# Low_Pass_Filter.net
KiCad netlist of a schematic drawn in Altium Designer
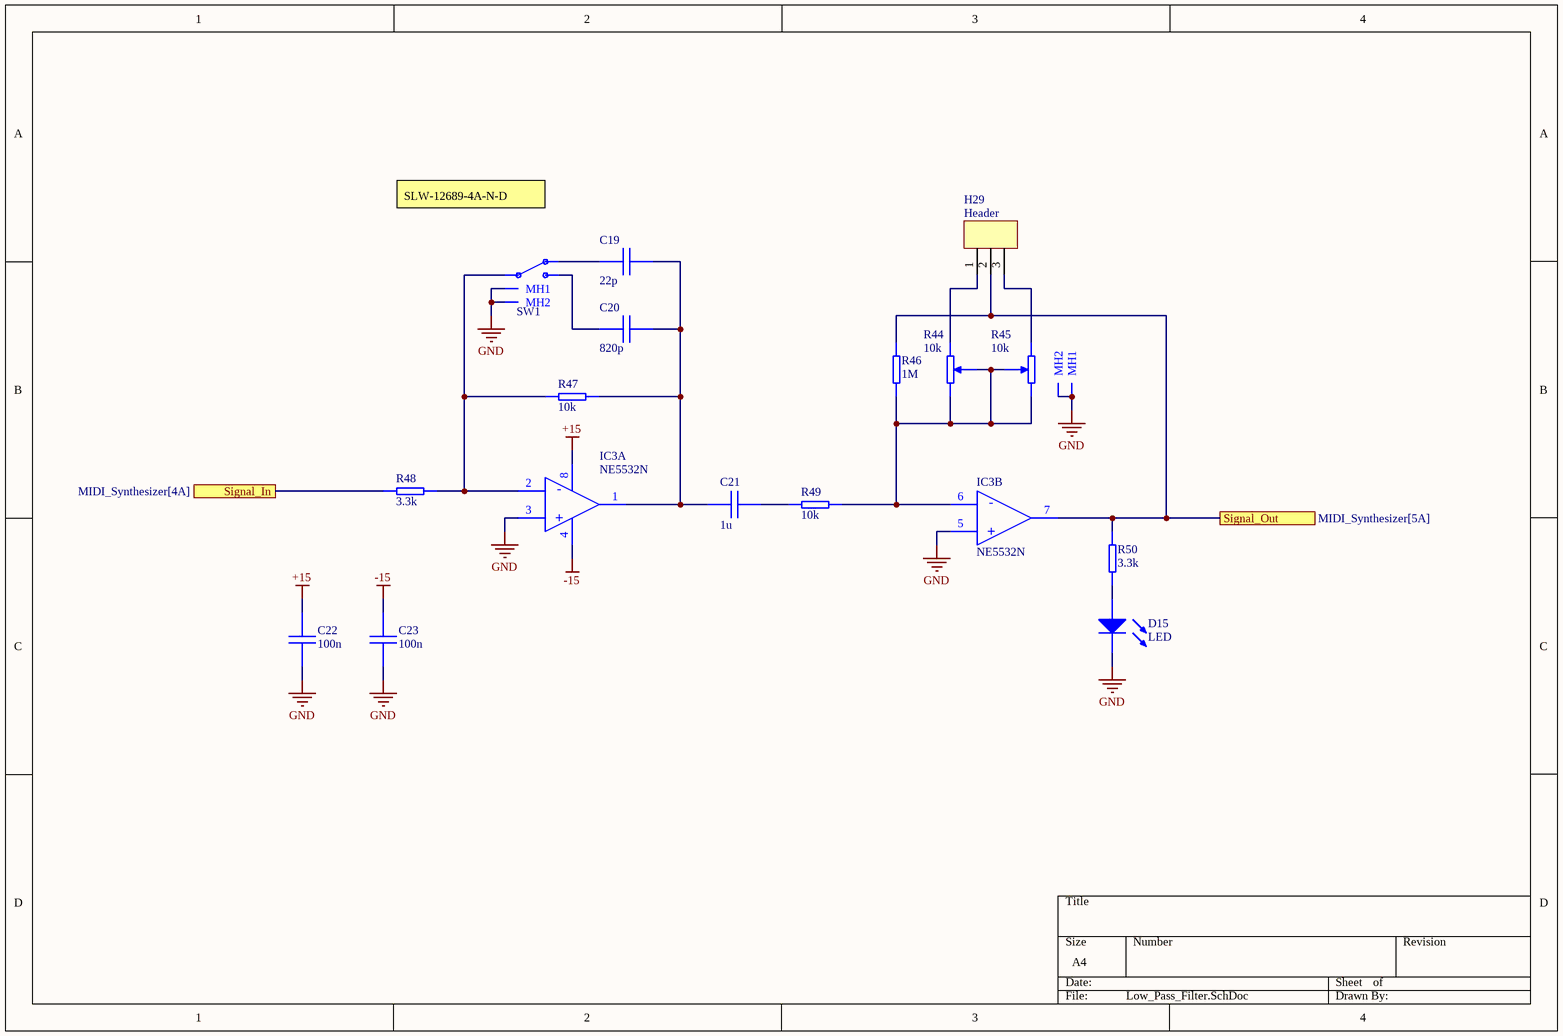
[diagram p0: Low_Pass_Filter.SchDoc]

(export (version "E")
  (design (tool "Eeschema 10.0.6"))
  (components
    (comp (ref "C19")
      (value "22p")
      (footprint "CAP0603")
      (description "Non Polarized Capacitor")
      (libsource (lib "TD") (part "Capacitor - Non Polarized"))
    )
    (comp (ref "C20")
      (value "820p")
      (footprint "CAP0603")
      (description "Non Polarized Capacitor")
      (libsource (lib "TD") (part "Capacitor - Non Polarized"))
    )
    (comp (ref "C21")
      (value "1u")
      (footprint "CAP0805")
      (description "Non Polarized Capacitor")
      (libsource (lib "TD") (part "Capacitor - Non Polarized"))
    )
    (comp (ref "C22")
      (value "100n")
      (footprint "CAP0805")
      (description "Non Polarized Capacitor")
      (libsource (lib "TD") (part "Capacitor - Non Polarized"))
    )
    (comp (ref "C23")
      (value "100n")
      (footprint "CAP0805")
      (description "Non Polarized Capacitor")
      (libsource (lib "TD") (part "Capacitor - Non Polarized"))
    )
    (comp (ref "D15")
      (value "LED")
      (footprint "LEDM1608X90N")
      (description "General Purpose LED")
      (libsource (lib "TD") (part "LED"))
    )
    (comp (ref "H29")
      (value "Header")
      (footprint "Header_1X3")
      (description "3-Pin Header")
      (libsource (lib "TD") (part "3-Pin Header"))
    )
    (comp (ref "IC3")
      (value "NE5532N")
      (footprint "DIP8")
      (description "Integrated Circuit")
      (fields (field (name "MOUSER PART NUMBER") "863-NE5532N"))
      (libsource (lib "TD") (part "NE5532N"))
    )
    (comp (ref "R44")
      (value "10k")
      (footprint "Trim_Pot_Hybrid - No_Silk")
      (description "Potentionmeter")
      (libsource (lib "TD") (part "Potentiometer"))
    )
    (comp (ref "R45")
      (value "10k")
      (footprint "PTV09A4015FB103")
      (description "Potentionmeter")
      (libsource (lib "TD") (part "Potentiometer_Mounted"))
    )
    (comp (ref "R46")
      (value "1M")
      (footprint "RESC0805")
      (description "Resistor")
      (libsource (lib "TD") (part "Resistor"))
    )
    (comp (ref "R47")
      (value "10k")
      (footprint "RESC0805")
      (description "Resistor")
      (libsource (lib "TD") (part "Resistor"))
    )
    (comp (ref "R48")
      (value "3.3k")
      (footprint "RESC0805")
      (description "Resistor")
      (libsource (lib "TD") (part "Resistor"))
    )
    (comp (ref "R49")
      (value "10k")
      (footprint "RESC0805")
      (description "Resistor")
      (libsource (lib "TD") (part "Resistor"))
    )
    (comp (ref "R50")
      (value "3.3k")
      (footprint "RESC0805")
      (description "Resistor")
      (libsource (lib "HT2.2") (part "Resistor"))
    )
    (comp (ref "SW1")
      (value "Slide Switch 4")
      (footprint "SLW126894AND")
      (description "Slide Switch")
      (libsource (lib "TD") (part "Slide Switch 4"))
    )
  )
  (nets
    (net (code "1") (name "+15") (class "Default")
      (node (ref "C22") (pin "2") (pintype "passive"))
      (node (ref "IC3") (pin "8") (pinfunction "V+_8") (pintype "passive"))
    )
    (net (code "2") (name "-15") (class "Default")
      (node (ref "C23") (pin "2") (pintype "passive"))
      (node (ref "IC3") (pin "4") (pinfunction "V-_4") (pintype "passive"))
    )
    (net (code "3") (name "/Signal_In") (class "Default") (node (ref "R48") (pin "2") (pintype "passive")))
    (net (code "4") (name "/Signal_Out") (class "Default")
      (node (ref "H29") (pin "2") (pintype "passive"))
      (node (ref "IC3") (pin "7") (pinfunction "OUT_B_7") (pintype "passive"))
      (node (ref "R46") (pin "1") (pintype "passive"))
      (node (ref "R50") (pin "1") (pintype "passive"))
    )
    (net (code "5") (name "GND") (class "Default")
      (node (ref "C22") (pin "1") (pintype "passive"))
      (node (ref "C23") (pin "1") (pintype "passive"))
      (node (ref "D15") (pin "1") (pinfunction "K_1") (pintype "passive"))
      (node (ref "IC3") (pin "3") (pinfunction "+IN_A_3") (pintype "passive"))
      (node (ref "IC3") (pin "5") (pinfunction "+IN_B_5") (pintype "passive"))
      (node (ref "R45") (pin "4") (pinfunction "MH1_4") (pintype "passive"))
      (node (ref "R45") (pin "5") (pinfunction "MH2_5") (pintype "passive"))
      (node (ref "SW1") (pin "4") (pinfunction "MH1_4") (pintype "passive"))
      (node (ref "SW1") (pin "5") (pinfunction "MH2_5") (pintype "passive"))
    )
    (net (code "6") (name "Net-(C19-Pad1)") (class "Default")
      (node (ref "C19") (pin "1") (pintype "passive"))
      (node (ref "SW1") (pin "1") (pintype "passive"))
    )
    (net (code "7") (name "Net-(C20-Pad1)") (class "Default")
      (node (ref "C20") (pin "1") (pintype "passive"))
      (node (ref "SW1") (pin "3") (pintype "passive"))
    )
    (net (code "8") (name "Net-(C21-Pad2)") (class "Default")
      (node (ref "C21") (pin "2") (pintype "passive"))
      (node (ref "R49") (pin "2") (pintype "passive"))
    )
    (net (code "9") (name "Net-(D15-A)") (class "Default")
      (node (ref "D15") (pin "2") (pinfunction "A_2") (pintype "passive"))
      (node (ref "R50") (pin "2") (pintype "passive"))
    )
    (net (code "10") (name "Net-(H29-Pad1)") (class "Default")
      (node (ref "H29") (pin "1") (pintype "passive"))
      (node (ref "R44") (pin "1") (pintype "passive"))
    )
    (net (code "11") (name "Net-(H29-Pad3)") (class "Default")
      (node (ref "H29") (pin "3") (pintype "passive"))
      (node (ref "R45") (pin "1") (pintype "passive"))
    )
    (net (code "12") (name "Net-(IC3A--IN_A)") (class "Default")
      (node (ref "IC3") (pin "2") (pinfunction "-IN_A_2") (pintype "passive"))
      (node (ref "R47") (pin "2") (pintype "passive"))
      (node (ref "R48") (pin "1") (pintype "passive"))
      (node (ref "SW1") (pin "2") (pintype "passive"))
    )
    (net (code "13") (name "Net-(IC3A-OUT_A)") (class "Default")
      (node (ref "C19") (pin "2") (pintype "passive"))
      (node (ref "C20") (pin "2") (pintype "passive"))
      (node (ref "C21") (pin "1") (pintype "passive"))
      (node (ref "IC3") (pin "1") (pinfunction "OUT_A_1") (pintype "passive"))
      (node (ref "R47") (pin "1") (pintype "passive"))
    )
    (net (code "14") (name "Net-(IC3B--IN_B)") (class "Default")
      (node (ref "IC3") (pin "6") (pinfunction "-IN_B_6") (pintype "passive"))
      (node (ref "R44") (pin "2") (pintype "passive"))
      (node (ref "R44") (pin "3") (pintype "passive"))
      (node (ref "R45") (pin "2") (pintype "passive"))
      (node (ref "R45") (pin "3") (pintype "passive"))
      (node (ref "R46") (pin "2") (pintype "passive"))
      (node (ref "R49") (pin "1") (pintype "passive"))
    )
  )
)
